# zero_board.net
KiCad netlist of a schematic drawn in EAGLE
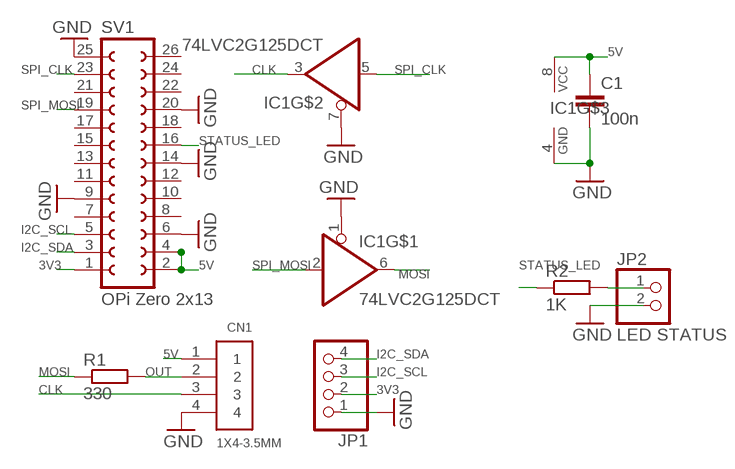
[diagram p0: schematic, sheet 1]

(export (version "E")
  (design (tool "Eeschema 10.0.6"))
  (components
    (comp (ref "C1")
      (value "100n")
      (footprint "eagle-import:C0805")
      (libsource (lib "eagle-import") (part "C-EUC0805"))
    )
    (comp (ref "CN1")
      (value "1X4-3.5MM")
      (footprint "eagle-import:1X04-3.5MM")
      (libsource (lib "eagle-import") (part "1X4-3.5MM"))
    )
    (comp (ref "IC1")
      (value "74LVC2G125DCT")
      (footprint "eagle-import:SSOP08")
      (libsource (lib "eagle-import") (part "742G125DCTLVC"))
    )
    (comp (ref "JP1")
      (value "PINHD-1X4")
      (footprint "eagle-import:1X04")
      (libsource (lib "eagle-import") (part "PINHD-1X4"))
    )
    (comp (ref "JP2")
      (value "LED STATUS")
      (footprint "eagle-import:1X02")
      (libsource (lib "eagle-import") (part "PINHD-1X2"))
    )
    (comp (ref "R1")
      (value "330")
      (footprint "eagle-import:R0805")
      (libsource (lib "eagle-import") (part "R-EU_R0805"))
    )
    (comp (ref "R2")
      (value "1K")
      (footprint "eagle-import:R0805")
      (libsource (lib "eagle-import") (part "R-EU_R0805"))
    )
    (comp (ref "SV1")
      (value "OPi Zero 2x13")
      (footprint "eagle-import:FE13-2")
      (libsource (lib "eagle-import") (part "FE13-2"))
    )
  )
  (nets
    (net (code "1") (name "/3V3") (class "Default")
      (node (ref "JP1") (pin "2") (pinfunction "2_2") (pintype "passive"))
      (node (ref "SV1") (pin "1") (pinfunction "1_1") (pintype "passive"))
    )
    (net (code "2") (name "/5V") (class "Default")
      (node (ref "C1") (pin "1") (pinfunction "1_1") (pintype "passive"))
      (node (ref "CN1") (pin "1") (pinfunction "1_1") (pintype "bidirectional"))
      (node (ref "IC1") (pin "8") (pinfunction "VCC_8") (pintype "power_in"))
      (node (ref "SV1") (pin "2") (pinfunction "2_2") (pintype "passive"))
      (node (ref "SV1") (pin "4") (pinfunction "4_4") (pintype "passive"))
    )
    (net (code "3") (name "/CLK") (class "Default")
      (node (ref "CN1") (pin "3") (pinfunction "3_3") (pintype "bidirectional"))
      (node (ref "IC1") (pin "3") (pinfunction "O_3") (pintype "tri_state"))
    )
    (net (code "4") (name "/I2C_SCL") (class "Default")
      (node (ref "JP1") (pin "3") (pinfunction "3_3") (pintype "passive"))
      (node (ref "SV1") (pin "5") (pinfunction "5_5") (pintype "passive"))
    )
    (net (code "5") (name "/I2C_SDA") (class "Default")
      (node (ref "JP1") (pin "4") (pinfunction "4_4") (pintype "passive"))
      (node (ref "SV1") (pin "3") (pinfunction "3_3") (pintype "passive"))
    )
    (net (code "6") (name "/MOSI") (class "Default")
      (node (ref "IC1") (pin "6") (pinfunction "O_6") (pintype "tri_state"))
      (node (ref "R1") (pin "1") (pinfunction "1_1") (pintype "passive"))
    )
    (net (code "7") (name "/OUT") (class "Default")
      (node (ref "CN1") (pin "2") (pinfunction "2_2") (pintype "bidirectional"))
      (node (ref "R1") (pin "2") (pinfunction "2_2") (pintype "passive"))
    )
    (net (code "8") (name "/SPI_CLK") (class "Default")
      (node (ref "IC1") (pin "5") (pinfunction "I_5") (pintype "input"))
      (node (ref "SV1") (pin "23") (pinfunction "23_23") (pintype "passive"))
    )
    (net (code "9") (name "/SPI_MOSI") (class "Default")
      (node (ref "IC1") (pin "2") (pinfunction "I_2") (pintype "input"))
      (node (ref "SV1") (pin "19") (pinfunction "19_19") (pintype "passive"))
    )
    (net (code "10") (name "/STATUS_LED") (class "Default")
      (node (ref "R2") (pin "1") (pinfunction "1_1") (pintype "passive"))
      (node (ref "SV1") (pin "16") (pinfunction "16_16") (pintype "passive"))
    )
    (net (code "11") (name "GND") (class "Default")
      (node (ref "C1") (pin "2") (pinfunction "2_2") (pintype "passive"))
      (node (ref "CN1") (pin "4") (pinfunction "4_4") (pintype "bidirectional"))
      (node (ref "IC1") (pin "1") (pinfunction "OE_1") (pintype "input"))
      (node (ref "IC1") (pin "4") (pinfunction "GND_4") (pintype "power_in"))
      (node (ref "IC1") (pin "7") (pinfunction "OE_7") (pintype "input"))
      (node (ref "JP1") (pin "1") (pinfunction "1_1") (pintype "passive"))
      (node (ref "JP2") (pin "2") (pinfunction "2_2") (pintype "passive"))
      (node (ref "SV1") (pin "14") (pinfunction "14_14") (pintype "passive"))
      (node (ref "SV1") (pin "20") (pinfunction "20_20") (pintype "passive"))
      (node (ref "SV1") (pin "25") (pinfunction "25_25") (pintype "passive"))
      (node (ref "SV1") (pin "6") (pinfunction "6_6") (pintype "passive"))
      (node (ref "SV1") (pin "9") (pinfunction "9_9") (pintype "passive"))
    )
    (net (code "12") (name "Net-(JP2-Pad1)") (class "Default")
      (node (ref "JP2") (pin "1") (pinfunction "1_1") (pintype "passive"))
      (node (ref "R2") (pin "2") (pinfunction "2_2") (pintype "passive"))
    )
    (net (code "13") (name "unconnected-(SV1-Pad7)") (class "Default")
      (node (ref "SV1") (pin "7") (pinfunction "7_7") (pintype "passive"))
    )
    (net (code "14") (name "unconnected-(SV1-Pad8)") (class "Default")
      (node (ref "SV1") (pin "8") (pinfunction "8_8") (pintype "passive"))
    )
    (net (code "15") (name "unconnected-(SV1-Pad10)") (class "Default")
      (node (ref "SV1") (pin "10") (pinfunction "10_10") (pintype "passive"))
    )
    (net (code "16") (name "unconnected-(SV1-Pad11)") (class "Default")
      (node (ref "SV1") (pin "11") (pinfunction "11_11") (pintype "passive"))
    )
    (net (code "17") (name "unconnected-(SV1-Pad12)") (class "Default")
      (node (ref "SV1") (pin "12") (pinfunction "12_12") (pintype "passive"))
    )
    (net (code "18") (name "unconnected-(SV1-Pad13)") (class "Default")
      (node (ref "SV1") (pin "13") (pinfunction "13_13") (pintype "passive"))
    )
    (net (code "19") (name "unconnected-(SV1-Pad15)") (class "Default")
      (node (ref "SV1") (pin "15") (pinfunction "15_15") (pintype "passive"))
    )
    (net (code "20") (name "unconnected-(SV1-Pad17)") (class "Default")
      (node (ref "SV1") (pin "17") (pinfunction "17_17") (pintype "passive"))
    )
    (net (code "21") (name "unconnected-(SV1-Pad18)") (class "Default")
      (node (ref "SV1") (pin "18") (pinfunction "18_18") (pintype "passive"))
    )
    (net (code "22") (name "unconnected-(SV1-Pad21)") (class "Default")
      (node (ref "SV1") (pin "21") (pinfunction "21_21") (pintype "passive"))
    )
    (net (code "23") (name "unconnected-(SV1-Pad22)") (class "Default")
      (node (ref "SV1") (pin "22") (pinfunction "22_22") (pintype "passive"))
    )
    (net (code "24") (name "unconnected-(SV1-Pad24)") (class "Default")
      (node (ref "SV1") (pin "24") (pinfunction "24_24") (pintype "passive"))
    )
    (net (code "25") (name "unconnected-(SV1-Pad26)") (class "Default")
      (node (ref "SV1") (pin "26") (pinfunction "26_26") (pintype "passive"))
    )
  )
)
